# Coursework_Tx.net
KiCad netlist of a schematic drawn in EAGLE
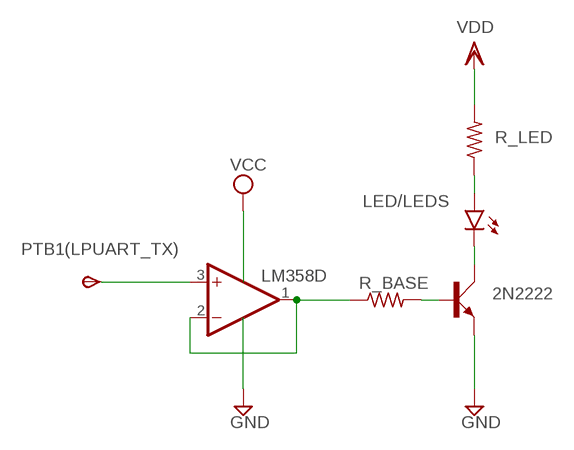
[diagram p0: schematic, sheet 1]

(export (version "E")
  (design (tool "Eeschema 10.0.6"))
  (components
    (comp (ref "IC1")
      (value "LM358D")
      (footprint "eagle-import:SO08")
      (fields (field (name "SPICEPREFIX") "J"))
      (libsource (lib "eagle-import") (part "LM358D"))
    )
    (comp (ref "LED/LEDS")
      (value "LED5MM")
      (footprint "eagle-import:LED5MM")
      (libsource (lib "eagle-import") (part "LED5MM"))
    )
    (comp (ref "PTB1(LPUART_TX)")
      (value "TPSB2,54")
      (footprint "eagle-import:B2,54")
      (libsource (lib "eagle-import") (part "TPSB2,54"))
    )
    (comp (ref "Q1")
      (value "2N2222")
      (footprint "eagle-import:TO18A")
      (libsource (lib "eagle-import") (part "2N2222"))
    )
    (comp (ref "R_BASE")
      (value "R-US_0204/5")
      (footprint "eagle-import:0204_5")
      (libsource (lib "eagle-import") (part "R-US_0204/5"))
    )
    (comp (ref "R_LED")
      (value "R-US_0204/5")
      (footprint "eagle-import:0204_5")
      (libsource (lib "eagle-import") (part "R-US_0204/5"))
    )
  )
  (nets
    (net (code "1") (name "GND") (class "Default")
      (node (ref "Q1") (pin "E") (pinfunction "E_E") (pintype "passive"))
    )
    (net (code "2") (name "Net-(IC1A-+IN)") (class "Default")
      (node (ref "IC1") (pin "3") (pinfunction "+IN_3") (pintype "input"))
      (node (ref "PTB1(LPUART_TX)") (pin "TP") (pinfunction "PP_TP") (pintype "input"))
    )
    (net (code "3") (name "Net-(IC1A--IN)") (class "Default")
      (node (ref "IC1") (pin "1") (pinfunction "OUT_1") (pintype "output"))
      (node (ref "IC1") (pin "2") (pinfunction "-IN_2") (pintype "input"))
      (node (ref "R_BASE") (pin "1") (pinfunction "1_1") (pintype "passive"))
    )
    (net (code "4") (name "Net-(LED/LEDS-C)") (class "Default")
      (node (ref "LED/LEDS") (pin "K") (pinfunction "C_K") (pintype "passive"))
      (node (ref "Q1") (pin "C") (pinfunction "C_C") (pintype "passive"))
    )
    (net (code "5") (name "Net-(LED/LEDS-PadA)") (class "Default")
      (node (ref "LED/LEDS") (pin "A") (pinfunction "A_A") (pintype "passive"))
      (node (ref "R_LED") (pin "1") (pinfunction "1_1") (pintype "passive"))
    )
    (net (code "6") (name "Net-(Q1-PadB)") (class "Default")
      (node (ref "Q1") (pin "B") (pinfunction "B_B") (pintype "passive"))
      (node (ref "R_BASE") (pin "2") (pinfunction "2_2") (pintype "passive"))
    )
    (net (code "8") (name "VDD") (class "Default")
      (node (ref "R_LED") (pin "2") (pinfunction "2_2") (pintype "passive"))
    )
  )
)
